# Motor_Surucu_V4.net
KiCad netlist of a schematic drawn in EAGLE
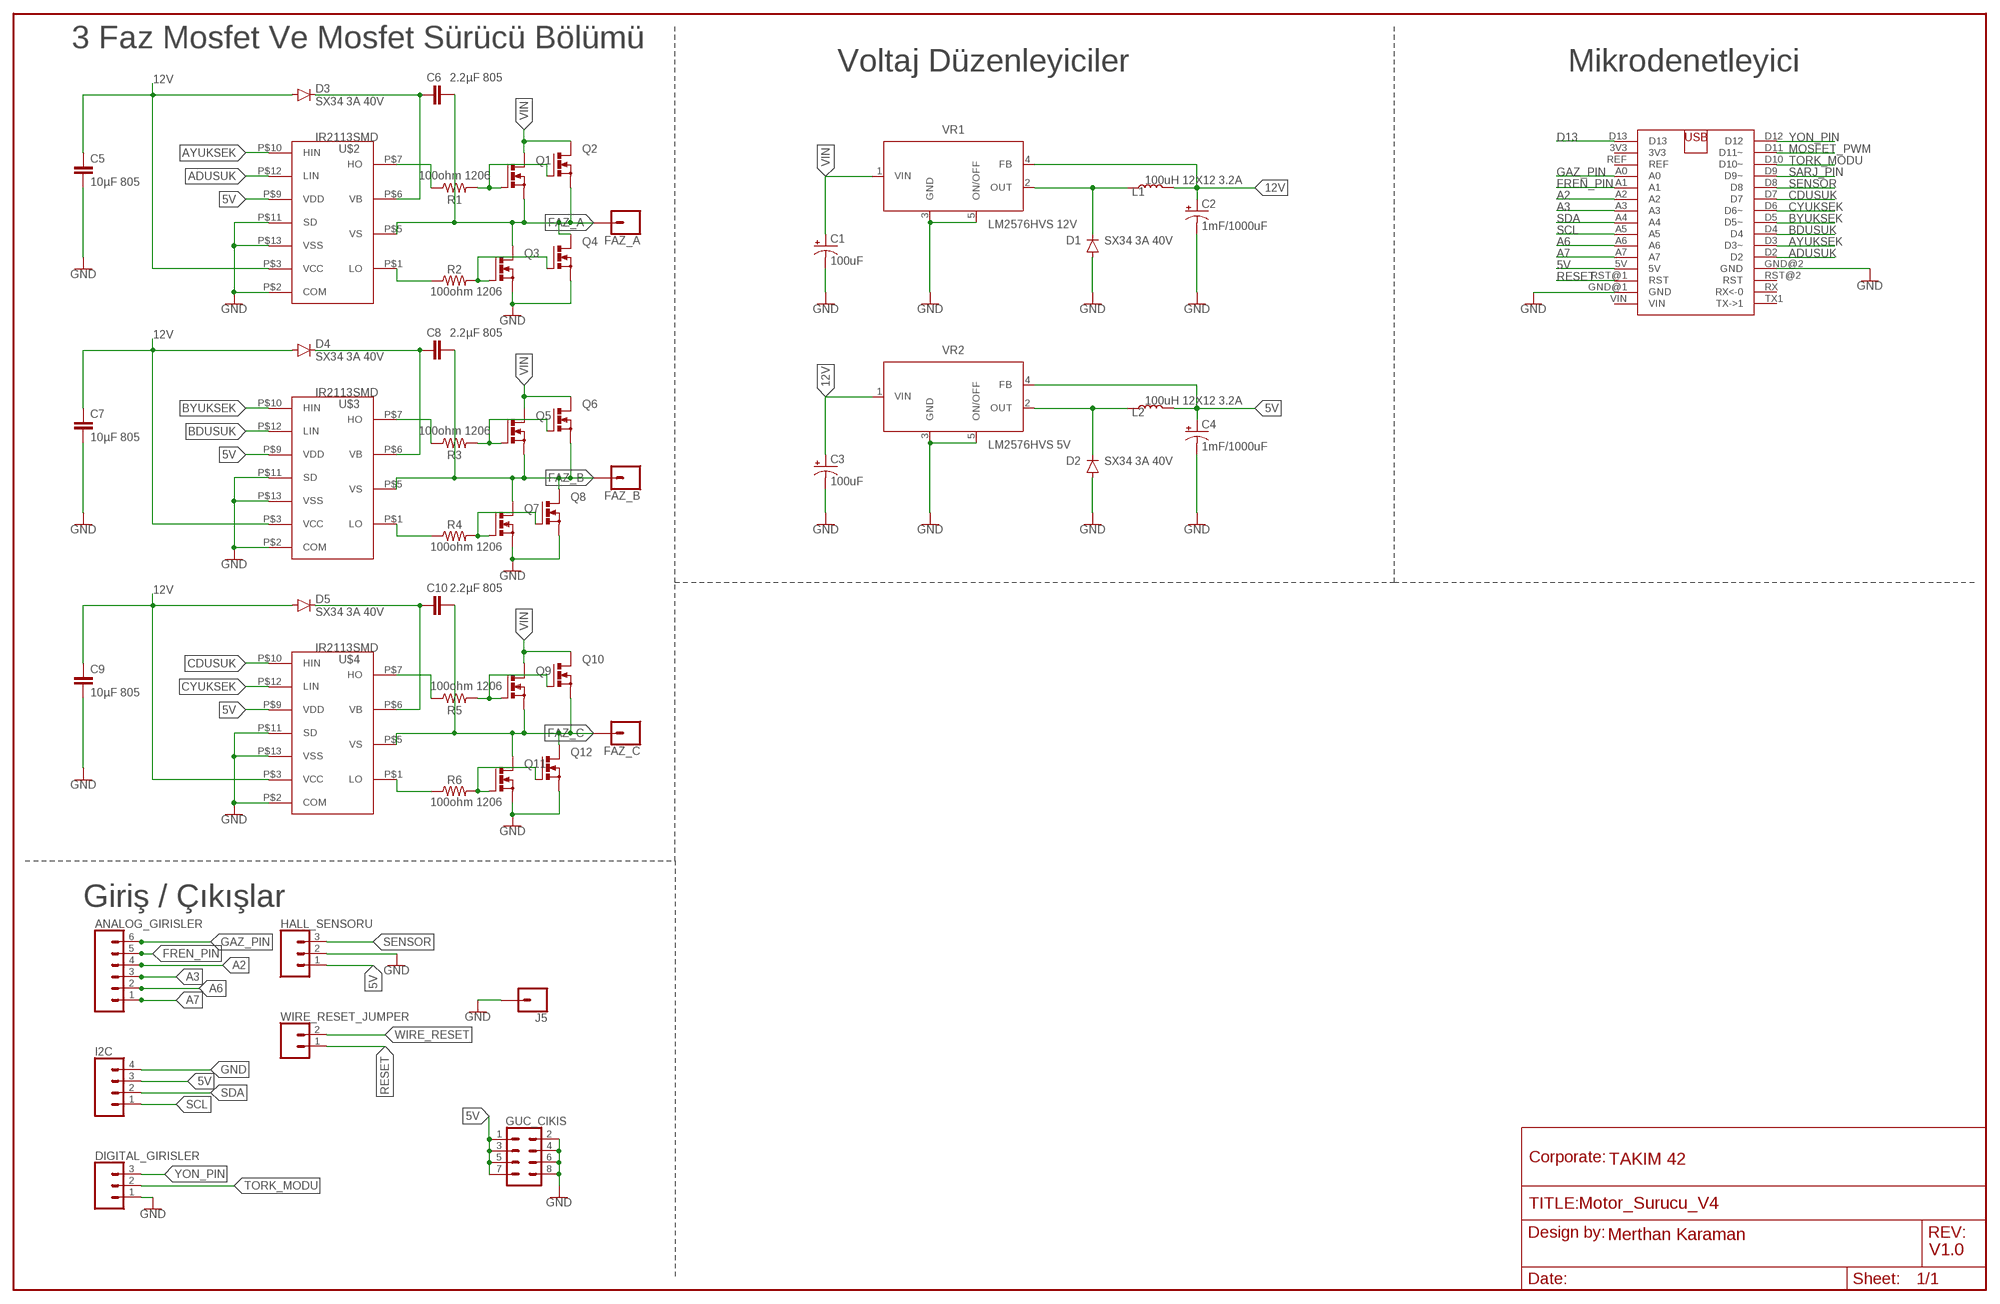
[diagram p0: schematic, sheet 1]

(export (version "E")
  (design (tool "Eeschema 10.0.6"))
  (components
    (comp (ref "ANALOG_GIRISLER")
      (value "CONN_06SILK_FEMALE_PTH")
      (footprint "eagle-import:1X06")
      (libsource (lib "eagle-import") (part "CONN_06SILK_FEMALE_PTH"))
    )
    (comp (ref "C1")
      (value "100uF")
      (footprint "eagle-import:CPOL-RADIAL-2.5MM-6.5MM")
      (libsource (lib "eagle-import") (part "100UF-POLAR-RADIAL-2.5MM-25V-20%"))
    )
    (comp (ref "C2")
      (value "1mF/1000uF")
      (footprint "eagle-import:PANASONIC_G")
      (libsource (lib "eagle-import") (part "560UF-PANASONIC_G-25V-20%"))
    )
    (comp (ref "C3")
      (value "100uF")
      (footprint "eagle-import:CPOL-RADIAL-2.5MM-6.5MM")
      (libsource (lib "eagle-import") (part "100UF-POLAR-RADIAL-2.5MM-25V-20%"))
    )
    (comp (ref "C4")
      (value "1mF/1000uF")
      (footprint "eagle-import:PANASONIC_G")
      (libsource (lib "eagle-import") (part "560UF-PANASONIC_G-25V-20%"))
    )
    (comp (ref "C5")
      (value "10µF 805")
      (footprint "eagle-import:0805")
      (libsource (lib "eagle-import") (part "0.33UF/330NF-0805-50V-10%"))
    )
    (comp (ref "C6")
      (value "2.2µF 805")
      (footprint "eagle-import:0805")
      (libsource (lib "eagle-import") (part "0.33UF/330NF-0805-50V-10%"))
    )
    (comp (ref "C7")
      (value "10µF 805")
      (footprint "eagle-import:0805")
      (libsource (lib "eagle-import") (part "0.33UF/330NF-0805-50V-10%"))
    )
    (comp (ref "C8")
      (value "2.2µF 805")
      (footprint "eagle-import:0805")
      (libsource (lib "eagle-import") (part "0.33UF/330NF-0805-50V-10%"))
    )
    (comp (ref "C9")
      (value "10µF 805")
      (footprint "eagle-import:0805")
      (libsource (lib "eagle-import") (part "0.33UF/330NF-0805-50V-10%"))
    )
    (comp (ref "C10")
      (value "2.2µF 805")
      (footprint "eagle-import:0805")
      (libsource (lib "eagle-import") (part "0.33UF/330NF-0805-50V-10%"))
    )
    (comp (ref "D1")
      (value "SX34 3A 40V")
      (footprint "eagle-import:DO214AC")
      (libsource (lib "eagle-import") (part "DIODE-DO214AC"))
    )
    (comp (ref "D2")
      (value "SX34 3A 40V")
      (footprint "eagle-import:DO214AC")
      (libsource (lib "eagle-import") (part "DIODE-DO214AC"))
    )
    (comp (ref "D3")
      (value "SX34 3A 40V")
      (footprint "eagle-import:DO214AC")
      (libsource (lib "eagle-import") (part "DIODE-DO214AC"))
    )
    (comp (ref "D4")
      (value "SX34 3A 40V")
      (footprint "eagle-import:DO214AC")
      (libsource (lib "eagle-import") (part "DIODE-DO214AC"))
    )
    (comp (ref "D5")
      (value "SX34 3A 40V")
      (footprint "eagle-import:DO214AC")
      (libsource (lib "eagle-import") (part "DIODE-DO214AC"))
    )
    (comp (ref "DIGITAL_GIRISLER")
      (value "CONN_03")
      (footprint "eagle-import:1X03")
      (libsource (lib "eagle-import") (part "CONN_03"))
    )
    (comp (ref "FAZ_A")
      (value "CONN_01SNAP-MALE")
      (footprint "eagle-import:SNAP-MALE")
      (libsource (lib "eagle-import") (part "CONN_01SNAP-MALE"))
    )
    (comp (ref "FAZ_B")
      (value "CONN_01SNAP-MALE")
      (footprint "eagle-import:SNAP-MALE")
      (libsource (lib "eagle-import") (part "CONN_01SNAP-MALE"))
    )
    (comp (ref "FAZ_C")
      (value "CONN_01SNAP-MALE")
      (footprint "eagle-import:SNAP-MALE")
      (libsource (lib "eagle-import") (part "CONN_01SNAP-MALE"))
    )
    (comp (ref "GUC_CIKIS")
      (value "CONN_04X2")
      (footprint "eagle-import:2X4")
      (libsource (lib "eagle-import") (part "CONN_04X2"))
    )
    (comp (ref "HALL_SENSORU")
      (value "CONN_03")
      (footprint "eagle-import:1X03")
      (libsource (lib "eagle-import") (part "CONN_03"))
    )
    (comp (ref "I2C")
      (value "CONN_04")
      (footprint "eagle-import:1X04")
      (libsource (lib "eagle-import") (part "CONN_04"))
    )
    (comp (ref "J5")
      (value "CONN_01SNAP-MALE")
      (footprint "eagle-import:SNAP-MALE")
      (libsource (lib "eagle-import") (part "CONN_01SNAP-MALE"))
    )
    (comp (ref "L1")
      (value "100uH 12X12 3.2A")
      (footprint "eagle-import:INDUCTOR_SDR1307")
      (libsource (lib "eagle-import") (part "INDUCTOR-SDR13-27UH"))
    )
    (comp (ref "L2")
      (value "100uH 12X12 3.2A")
      (footprint "eagle-import:INDUCTOR_SDR1307")
      (libsource (lib "eagle-import") (part "INDUCTOR-SDR13-27UH"))
    )
    (comp (ref "Q1")
      (value "PMOSFET_NTO220BV")
      (footprint "eagle-import:TO220BV")
      (libsource (lib "eagle-import") (part "PMOSFET_NTO220BV"))
    )
    (comp (ref "Q2")
      (value "PMOSFET_NTO220BV")
      (footprint "eagle-import:TO220BV")
      (libsource (lib "eagle-import") (part "PMOSFET_NTO220BV"))
    )
    (comp (ref "Q3")
      (value "PMOSFET_NTO220BV")
      (footprint "eagle-import:TO220BV")
      (libsource (lib "eagle-import") (part "PMOSFET_NTO220BV"))
    )
    (comp (ref "Q4")
      (value "PMOSFET_NTO220BV")
      (footprint "eagle-import:TO220BV")
      (libsource (lib "eagle-import") (part "PMOSFET_NTO220BV"))
    )
    (comp (ref "Q5")
      (value "PMOSFET_NTO220BV")
      (footprint "eagle-import:TO220BV")
      (libsource (lib "eagle-import") (part "PMOSFET_NTO220BV"))
    )
    (comp (ref "Q6")
      (value "PMOSFET_NTO220BV")
      (footprint "eagle-import:TO220BV")
      (libsource (lib "eagle-import") (part "PMOSFET_NTO220BV"))
    )
    (comp (ref "Q7")
      (value "PMOSFET_NTO220BV")
      (footprint "eagle-import:TO220BV")
      (libsource (lib "eagle-import") (part "PMOSFET_NTO220BV"))
    )
    (comp (ref "Q8")
      (value "PMOSFET_NTO220BV")
      (footprint "eagle-import:TO220BV")
      (libsource (lib "eagle-import") (part "PMOSFET_NTO220BV"))
    )
    (comp (ref "Q9")
      (value "PMOSFET_NTO220BV")
      (footprint "eagle-import:TO220BV")
      (libsource (lib "eagle-import") (part "PMOSFET_NTO220BV"))
    )
    (comp (ref "Q10")
      (value "PMOSFET_NTO220BV")
      (footprint "eagle-import:TO220BV")
      (libsource (lib "eagle-import") (part "PMOSFET_NTO220BV"))
    )
    (comp (ref "Q11")
      (value "PMOSFET_NTO220BV")
      (footprint "eagle-import:TO220BV")
      (libsource (lib "eagle-import") (part "PMOSFET_NTO220BV"))
    )
    (comp (ref "Q12")
      (value "PMOSFET_NTO220BV")
      (footprint "eagle-import:TO220BV")
      (libsource (lib "eagle-import") (part "PMOSFET_NTO220BV"))
    )
    (comp (ref "R1")
      (value "100ohm 1206")
      (footprint "eagle-import:1206")
      (libsource (lib "eagle-import") (part "RESISTOR1206"))
    )
    (comp (ref "R2")
      (value "100ohm 1206")
      (footprint "eagle-import:1206")
      (libsource (lib "eagle-import") (part "RESISTOR1206"))
    )
    (comp (ref "R3")
      (value "100ohm 1206")
      (footprint "eagle-import:1206")
      (libsource (lib "eagle-import") (part "RESISTOR1206"))
    )
    (comp (ref "R4")
      (value "100ohm 1206")
      (footprint "eagle-import:1206")
      (libsource (lib "eagle-import") (part "RESISTOR1206"))
    )
    (comp (ref "R5")
      (value "100ohm 1206")
      (footprint "eagle-import:1206")
      (libsource (lib "eagle-import") (part "RESISTOR1206"))
    )
    (comp (ref "R6")
      (value "100ohm 1206")
      (footprint "eagle-import:1206")
      (libsource (lib "eagle-import") (part "RESISTOR1206"))
    )
    (comp (ref "U$1")
      (value "ARDUINO_NANO")
      (footprint "eagle-import:ARDUINO_NANO")
      (libsource (lib "eagle-import") (part "ARDUINO_NANO"))
    )
    (comp (ref "U$2")
      (value "IR2113SMD")
      (footprint "eagle-import:SOIC-14")
      (libsource (lib "eagle-import") (part "IR2113SMD"))
    )
    (comp (ref "U$3")
      (value "IR2113SMD")
      (footprint "eagle-import:SOIC-14")
      (libsource (lib "eagle-import") (part "IR2113SMD"))
    )
    (comp (ref "U$4")
      (value "IR2113SMD")
      (footprint "eagle-import:SOIC-14")
      (libsource (lib "eagle-import") (part "IR2113SMD"))
    )
    (comp (ref "VR1")
      (value "LM2576HVS 12V")
      (footprint "eagle-import:TO170P1435X465-6N")
      (fields (field (name "MANUFACTURER") "TI") (field (name "MPN") "LM2576HVS-5.0/NOPB"))
      (libsource (lib "eagle-import") (part "LM2576HVS-5.0/NOPBTO-263"))
    )
    (comp (ref "VR2")
      (value "LM2576HVS 5V")
      (footprint "eagle-import:TO170P1435X465-6N")
      (fields (field (name "MANUFACTURER") "TI") (field (name "MPN") "LM2576HVS-5.0/NOPB"))
      (libsource (lib "eagle-import") (part "LM2576HVS-5.0/NOPBTO-263"))
    )
    (comp (ref "WIRE_RESET_JUMPER")
      (value "CONN_02")
      (footprint "eagle-import:1X02")
      (libsource (lib "eagle-import") (part "CONN_02"))
    )
  )
  (nets
    (net (code "1") (name "/D13") (class "Default")
      (node (ref "U$1") (pin "D13") (pinfunction "D13_D13") (pintype "bidirectional"))
    )
    (net (code "2") (name "/MOSFET_PWM") (class "Default")
      (node (ref "U$1") (pin "D11") (pinfunction "D11~{}_D11") (pintype "bidirectional"))
    )
    (net (code "3") (name "/SARJ_PIN") (class "Default")
      (node (ref "U$1") (pin "D9") (pinfunction "D9~{}_D9") (pintype "bidirectional"))
    )
    (net (code "4") (name "5V") (class "Default")
      (node (ref "C4") (pin "+") (pinfunction "+_+") (pintype "passive"))
      (node (ref "GUC_CIKIS") (pin "1") (pinfunction "1_1") (pintype "passive"))
      (node (ref "GUC_CIKIS") (pin "3") (pinfunction "3_3") (pintype "passive"))
      (node (ref "GUC_CIKIS") (pin "5") (pinfunction "5_5") (pintype "passive"))
      (node (ref "GUC_CIKIS") (pin "7") (pinfunction "7_7") (pintype "passive"))
      (node (ref "HALL_SENSORU") (pin "1") (pinfunction "1_1") (pintype "passive"))
      (node (ref "I2C") (pin "3") (pinfunction "3_3") (pintype "passive"))
      (node (ref "L2") (pin "P$2") (pinfunction "2_P$2") (pintype "passive"))
      (node (ref "U$1") (pin "5V") (pinfunction "5V_5V") (pintype "bidirectional"))
      (node (ref "U$2") (pin "P$9") (pinfunction "VDD_P$9") (pintype "bidirectional"))
      (node (ref "U$3") (pin "P$9") (pinfunction "VDD_P$9") (pintype "bidirectional"))
      (node (ref "U$4") (pin "P$9") (pinfunction "VDD_P$9") (pintype "bidirectional"))
      (node (ref "VR2") (pin "4") (pinfunction "FB_4") (pintype "output"))
    )
    (net (code "5") (name "12V") (class "Default")
      (node (ref "C2") (pin "+") (pinfunction "+_+") (pintype "passive"))
      (node (ref "C3") (pin "1") (pinfunction "+_1") (pintype "passive"))
      (node (ref "C5") (pin "1") (pinfunction "1_1") (pintype "passive"))
      (node (ref "C7") (pin "1") (pinfunction "1_1") (pintype "passive"))
      (node (ref "C9") (pin "1") (pinfunction "1_1") (pintype "passive"))
      (node (ref "D3") (pin "A") (pinfunction "A_A") (pintype "passive"))
      (node (ref "D4") (pin "A") (pinfunction "A_A") (pintype "passive"))
      (node (ref "D5") (pin "A") (pinfunction "A_A") (pintype "passive"))
      (node (ref "L1") (pin "P$2") (pinfunction "2_P$2") (pintype "passive"))
      (node (ref "U$2") (pin "P$3") (pinfunction "VCC_P$3") (pintype "bidirectional"))
      (node (ref "U$3") (pin "P$3") (pinfunction "VCC_P$3") (pintype "bidirectional"))
      (node (ref "U$4") (pin "P$3") (pinfunction "VCC_P$3") (pintype "bidirectional"))
      (node (ref "VR1") (pin "4") (pinfunction "FB_4") (pintype "output"))
      (node (ref "VR2") (pin "1") (pinfunction "VIN_1") (pintype "input"))
    )
    (net (code "6") (name "A2") (class "Default")
      (node (ref "ANALOG_GIRISLER") (pin "4") (pinfunction "4_4") (pintype "passive"))
      (node (ref "U$1") (pin "A2") (pinfunction "A2_A2") (pintype "bidirectional"))
    )
    (net (code "7") (name "A3") (class "Default")
      (node (ref "ANALOG_GIRISLER") (pin "3") (pinfunction "3_3") (pintype "passive"))
      (node (ref "U$1") (pin "A3") (pinfunction "A3_A3") (pintype "bidirectional"))
    )
    (net (code "8") (name "A6") (class "Default")
      (node (ref "ANALOG_GIRISLER") (pin "2") (pinfunction "2_2") (pintype "passive"))
      (node (ref "U$1") (pin "A6") (pinfunction "A6_A6") (pintype "bidirectional"))
    )
    (net (code "9") (name "A7") (class "Default")
      (node (ref "ANALOG_GIRISLER") (pin "1") (pinfunction "1_1") (pintype "passive"))
      (node (ref "U$1") (pin "A7") (pinfunction "A7_A7") (pintype "bidirectional"))
    )
    (net (code "10") (name "ADUSUK") (class "Default")
      (node (ref "U$1") (pin "D2") (pinfunction "D2_D2") (pintype "bidirectional"))
      (node (ref "U$2") (pin "P$12") (pinfunction "LIN_P$12") (pintype "bidirectional"))
    )
    (net (code "11") (name "AYUKSEK") (class "Default")
      (node (ref "U$1") (pin "D3") (pinfunction "D3~{}_D3") (pintype "bidirectional"))
      (node (ref "U$2") (pin "P$10") (pinfunction "HIN_P$10") (pintype "bidirectional"))
    )
    (net (code "12") (name "BDUSUK") (class "Default")
      (node (ref "U$1") (pin "D4") (pinfunction "D4_D4") (pintype "bidirectional"))
      (node (ref "U$3") (pin "P$12") (pinfunction "LIN_P$12") (pintype "bidirectional"))
    )
    (net (code "13") (name "BYUKSEK") (class "Default")
      (node (ref "U$1") (pin "D5") (pinfunction "D5~{}_D5") (pintype "bidirectional"))
      (node (ref "U$3") (pin "P$10") (pinfunction "HIN_P$10") (pintype "bidirectional"))
    )
    (net (code "14") (name "CDUSUK") (class "Default")
      (node (ref "U$1") (pin "D7") (pinfunction "D7_D7") (pintype "bidirectional"))
      (node (ref "U$4") (pin "P$10") (pinfunction "HIN_P$10") (pintype "bidirectional"))
    )
    (net (code "15") (name "CYUKSEK") (class "Default")
      (node (ref "U$1") (pin "D6") (pinfunction "D6~{}_D6") (pintype "bidirectional"))
      (node (ref "U$4") (pin "P$12") (pinfunction "LIN_P$12") (pintype "bidirectional"))
    )
    (net (code "16") (name "FAZ_A") (class "Default")
      (node (ref "C6") (pin "2") (pinfunction "2_2") (pintype "passive"))
      (node (ref "FAZ_A") (pin "2") (pinfunction "1_2") (pintype "passive"))
      (node (ref "Q1") (pin "S") (pinfunction "S_S") (pintype "passive"))
      (node (ref "Q2") (pin "S") (pinfunction "S_S") (pintype "passive"))
      (node (ref "Q3") (pin "D") (pinfunction "D_D") (pintype "passive"))
      (node (ref "Q4") (pin "D") (pinfunction "D_D") (pintype "passive"))
      (node (ref "U$2") (pin "P$5") (pinfunction "VS_P$5") (pintype "bidirectional"))
    )
    (net (code "17") (name "FAZ_B") (class "Default")
      (node (ref "C8") (pin "2") (pinfunction "2_2") (pintype "passive"))
      (node (ref "FAZ_B") (pin "2") (pinfunction "1_2") (pintype "passive"))
      (node (ref "Q5") (pin "S") (pinfunction "S_S") (pintype "passive"))
      (node (ref "Q6") (pin "S") (pinfunction "S_S") (pintype "passive"))
      (node (ref "Q7") (pin "D") (pinfunction "D_D") (pintype "passive"))
      (node (ref "Q8") (pin "D") (pinfunction "D_D") (pintype "passive"))
      (node (ref "U$3") (pin "P$5") (pinfunction "VS_P$5") (pintype "bidirectional"))
    )
    (net (code "18") (name "FAZ_C") (class "Default")
      (node (ref "C10") (pin "2") (pinfunction "2_2") (pintype "passive"))
      (node (ref "FAZ_C") (pin "2") (pinfunction "1_2") (pintype "passive"))
      (node (ref "Q10") (pin "S") (pinfunction "S_S") (pintype "passive"))
      (node (ref "Q11") (pin "D") (pinfunction "D_D") (pintype "passive"))
      (node (ref "Q12") (pin "D") (pinfunction "D_D") (pintype "passive"))
      (node (ref "Q9") (pin "S") (pinfunction "S_S") (pintype "passive"))
      (node (ref "U$4") (pin "P$5") (pinfunction "VS_P$5") (pintype "bidirectional"))
    )
    (net (code "19") (name "FREN_PIN") (class "Default")
      (node (ref "ANALOG_GIRISLER") (pin "5") (pinfunction "5_5") (pintype "passive"))
      (node (ref "U$1") (pin "A1") (pinfunction "A1_A1") (pintype "bidirectional"))
    )
    (net (code "20") (name "GAZ_PIN") (class "Default")
      (node (ref "ANALOG_GIRISLER") (pin "6") (pinfunction "6_6") (pintype "passive"))
      (node (ref "U$1") (pin "A0") (pinfunction "A0_A0") (pintype "bidirectional"))
    )
    (net (code "21") (name "GND") (class "Default")
      (node (ref "C1") (pin "2") (pinfunction "-_2") (pintype "passive"))
      (node (ref "C2") (pin "-") (pinfunction "-_-") (pintype "passive"))
      (node (ref "C3") (pin "2") (pinfunction "-_2") (pintype "passive"))
      (node (ref "C4") (pin "-") (pinfunction "-_-") (pintype "passive"))
      (node (ref "C5") (pin "2") (pinfunction "2_2") (pintype "passive"))
      (node (ref "C7") (pin "2") (pinfunction "2_2") (pintype "passive"))
      (node (ref "C9") (pin "2") (pinfunction "2_2") (pintype "passive"))
      (node (ref "D1") (pin "A") (pinfunction "A_A") (pintype "passive"))
      (node (ref "D2") (pin "A") (pinfunction "A_A") (pintype "passive"))
      (node (ref "DIGITAL_GIRISLER") (pin "1") (pinfunction "1_1") (pintype "passive"))
      (node (ref "GUC_CIKIS") (pin "2") (pinfunction "2_2") (pintype "passive"))
      (node (ref "GUC_CIKIS") (pin "4") (pinfunction "4_4") (pintype "passive"))
      (node (ref "GUC_CIKIS") (pin "6") (pinfunction "6_6") (pintype "passive"))
      (node (ref "GUC_CIKIS") (pin "8") (pinfunction "8_8") (pintype "passive"))
      (node (ref "HALL_SENSORU") (pin "2") (pinfunction "2_2") (pintype "passive"))
      (node (ref "I2C") (pin "4") (pinfunction "4_4") (pintype "passive"))
      (node (ref "J5") (pin "2") (pinfunction "1_2") (pintype "passive"))
      (node (ref "Q11") (pin "S") (pinfunction "S_S") (pintype "passive"))
      (node (ref "Q12") (pin "S") (pinfunction "S_S") (pintype "passive"))
      (node (ref "Q3") (pin "S") (pinfunction "S_S") (pintype "passive"))
      (node (ref "Q4") (pin "S") (pinfunction "S_S") (pintype "passive"))
      (node (ref "Q7") (pin "S") (pinfunction "S_S") (pintype "passive"))
      (node (ref "Q8") (pin "S") (pinfunction "S_S") (pintype "passive"))
      (node (ref "U$1") (pin "GND@1") (pinfunction "GND_GND@1") (pintype "bidirectional"))
      (node (ref "U$1") (pin "GND@2") (pinfunction "GND_GND@2") (pintype "bidirectional"))
      (node (ref "U$2") (pin "P$11") (pinfunction "SD_P$11") (pintype "bidirectional"))
      (node (ref "U$2") (pin "P$13") (pinfunction "VSS_P$13") (pintype "bidirectional"))
      (node (ref "U$2") (pin "P$2") (pinfunction "COM_P$2") (pintype "bidirectional"))
      (node (ref "U$3") (pin "P$11") (pinfunction "SD_P$11") (pintype "bidirectional"))
      (node (ref "U$3") (pin "P$13") (pinfunction "VSS_P$13") (pintype "bidirectional"))
      (node (ref "U$3") (pin "P$2") (pinfunction "COM_P$2") (pintype "bidirectional"))
      (node (ref "U$4") (pin "P$11") (pinfunction "SD_P$11") (pintype "bidirectional"))
      (node (ref "U$4") (pin "P$13") (pinfunction "VSS_P$13") (pintype "bidirectional"))
      (node (ref "U$4") (pin "P$2") (pinfunction "COM_P$2") (pintype "bidirectional"))
      (node (ref "VR1") (pin "3") (pinfunction "GND_3") (pintype "passive"))
      (node (ref "VR1") (pin "5") (pinfunction "ON/OFF_5") (pintype "input"))
      (node (ref "VR2") (pin "3") (pinfunction "GND_3") (pintype "passive"))
      (node (ref "VR2") (pin "5") (pinfunction "ON/OFF_5") (pintype "input"))
    )
    (net (code "22") (name "Net-(L1-1)") (class "Default")
      (node (ref "D1") (pin "C") (pinfunction "C_C") (pintype "passive"))
      (node (ref "L1") (pin "P$1") (pinfunction "1_P$1") (pintype "passive"))
      (node (ref "VR1") (pin "2") (pinfunction "OUT_2") (pintype "output"))
    )
    (net (code "23") (name "Net-(L2-1)") (class "Default")
      (node (ref "D2") (pin "C") (pinfunction "C_C") (pintype "passive"))
      (node (ref "L2") (pin "P$1") (pinfunction "1_P$1") (pintype "passive"))
      (node (ref "VR2") (pin "2") (pinfunction "OUT_2") (pintype "output"))
    )
    (net (code "24") (name "Net-(Q1-PadG)") (class "Default")
      (node (ref "Q1") (pin "G") (pinfunction "G_G") (pintype "passive"))
      (node (ref "Q2") (pin "G") (pinfunction "G_G") (pintype "passive"))
      (node (ref "R1") (pin "2") (pinfunction "2_2") (pintype "passive"))
    )
    (net (code "25") (name "Net-(Q3-PadG)") (class "Default")
      (node (ref "Q3") (pin "G") (pinfunction "G_G") (pintype "passive"))
      (node (ref "Q4") (pin "G") (pinfunction "G_G") (pintype "passive"))
      (node (ref "R2") (pin "2") (pinfunction "2_2") (pintype "passive"))
    )
    (net (code "26") (name "Net-(Q5-PadG)") (class "Default")
      (node (ref "Q5") (pin "G") (pinfunction "G_G") (pintype "passive"))
      (node (ref "Q6") (pin "G") (pinfunction "G_G") (pintype "passive"))
      (node (ref "R3") (pin "2") (pinfunction "2_2") (pintype "passive"))
    )
    (net (code "27") (name "Net-(Q7-PadG)") (class "Default")
      (node (ref "Q7") (pin "G") (pinfunction "G_G") (pintype "passive"))
      (node (ref "Q8") (pin "G") (pinfunction "G_G") (pintype "passive"))
      (node (ref "R4") (pin "2") (pinfunction "2_2") (pintype "passive"))
    )
    (net (code "28") (name "Net-(Q10-PadG)") (class "Default")
      (node (ref "Q10") (pin "G") (pinfunction "G_G") (pintype "passive"))
      (node (ref "Q9") (pin "G") (pinfunction "G_G") (pintype "passive"))
      (node (ref "R5") (pin "2") (pinfunction "2_2") (pintype "passive"))
    )
    (net (code "29") (name "Net-(Q11-PadG)") (class "Default")
      (node (ref "Q11") (pin "G") (pinfunction "G_G") (pintype "passive"))
      (node (ref "Q12") (pin "G") (pinfunction "G_G") (pintype "passive"))
      (node (ref "R6") (pin "2") (pinfunction "2_2") (pintype "passive"))
    )
    (net (code "30") (name "Net-(U$2-HO)") (class "Default")
      (node (ref "R1") (pin "1") (pinfunction "1_1") (pintype "passive"))
      (node (ref "U$2") (pin "P$7") (pinfunction "HO_P$7") (pintype "bidirectional"))
    )
    (net (code "31") (name "Net-(U$2-LO)") (class "Default")
      (node (ref "R2") (pin "1") (pinfunction "1_1") (pintype "passive"))
      (node (ref "U$2") (pin "P$1") (pinfunction "LO_P$1") (pintype "bidirectional"))
    )
    (net (code "32") (name "Net-(U$2-VB)") (class "Default")
      (node (ref "C6") (pin "1") (pinfunction "1_1") (pintype "passive"))
      (node (ref "D3") (pin "C") (pinfunction "C_C") (pintype "passive"))
      (node (ref "U$2") (pin "P$6") (pinfunction "VB_P$6") (pintype "bidirectional"))
    )
    (net (code "33") (name "Net-(U$3-HO)") (class "Default")
      (node (ref "R3") (pin "1") (pinfunction "1_1") (pintype "passive"))
      (node (ref "U$3") (pin "P$7") (pinfunction "HO_P$7") (pintype "bidirectional"))
    )
    (net (code "34") (name "Net-(U$3-LO)") (class "Default")
      (node (ref "R4") (pin "1") (pinfunction "1_1") (pintype "passive"))
      (node (ref "U$3") (pin "P$1") (pinfunction "LO_P$1") (pintype "bidirectional"))
    )
    (net (code "35") (name "Net-(U$3-VB)") (class "Default")
      (node (ref "C8") (pin "1") (pinfunction "1_1") (pintype "passive"))
      (node (ref "D4") (pin "C") (pinfunction "C_C") (pintype "passive"))
      (node (ref "U$3") (pin "P$6") (pinfunction "VB_P$6") (pintype "bidirectional"))
    )
    (net (code "36") (name "Net-(U$4-HO)") (class "Default")
      (node (ref "R5") (pin "1") (pinfunction "1_1") (pintype "passive"))
      (node (ref "U$4") (pin "P$7") (pinfunction "HO_P$7") (pintype "bidirectional"))
    )
    (net (code "37") (name "Net-(U$4-LO)") (class "Default")
      (node (ref "R6") (pin "1") (pinfunction "1_1") (pintype "passive"))
      (node (ref "U$4") (pin "P$1") (pinfunction "LO_P$1") (pintype "bidirectional"))
    )
    (net (code "38") (name "Net-(U$4-VB)") (class "Default")
      (node (ref "C10") (pin "1") (pinfunction "1_1") (pintype "passive"))
      (node (ref "D5") (pin "C") (pinfunction "C_C") (pintype "passive"))
      (node (ref "U$4") (pin "P$6") (pinfunction "VB_P$6") (pintype "bidirectional"))
    )
    (net (code "39") (name "RESET") (class "Default")
      (node (ref "U$1") (pin "RST@1") (pinfunction "RST_RST@1") (pintype "bidirectional"))
      (node (ref "WIRE_RESET_JUMPER") (pin "1") (pinfunction "1_1") (pintype "passive"))
    )
    (net (code "40") (name "SCL") (class "Default")
      (node (ref "I2C") (pin "1") (pinfunction "1_1") (pintype "passive"))
      (node (ref "U$1") (pin "A5") (pinfunction "A5_A5") (pintype "bidirectional"))
    )
    (net (code "41") (name "SDA") (class "Default")
      (node (ref "I2C") (pin "2") (pinfunction "2_2") (pintype "passive"))
      (node (ref "U$1") (pin "A4") (pinfunction "A4_A4") (pintype "bidirectional"))
    )
    (net (code "42") (name "SENSOR") (class "Default")
      (node (ref "HALL_SENSORU") (pin "3") (pinfunction "3_3") (pintype "passive"))
      (node (ref "U$1") (pin "D8") (pinfunction "D8_D8") (pintype "bidirectional"))
    )
    (net (code "43") (name "TORK_MODU") (class "Default")
      (node (ref "DIGITAL_GIRISLER") (pin "2") (pinfunction "2_2") (pintype "passive"))
      (node (ref "U$1") (pin "D10") (pinfunction "D10~{}_D10") (pintype "bidirectional"))
    )
    (net (code "44") (name "VIN") (class "Default")
      (node (ref "C1") (pin "1") (pinfunction "+_1") (pintype "passive"))
      (node (ref "Q1") (pin "D") (pinfunction "D_D") (pintype "passive"))
      (node (ref "Q10") (pin "D") (pinfunction "D_D") (pintype "passive"))
      (node (ref "Q2") (pin "D") (pinfunction "D_D") (pintype "passive"))
      (node (ref "Q5") (pin "D") (pinfunction "D_D") (pintype "passive"))
      (node (ref "Q6") (pin "D") (pinfunction "D_D") (pintype "passive"))
      (node (ref "Q9") (pin "D") (pinfunction "D_D") (pintype "passive"))
      (node (ref "VR1") (pin "1") (pinfunction "VIN_1") (pintype "input"))
    )
    (net (code "45") (name "WIRE_RESET") (class "Default")
      (node (ref "WIRE_RESET_JUMPER") (pin "2") (pinfunction "2_2") (pintype "passive"))
    )
    (net (code "46") (name "YON_PIN") (class "Default")
      (node (ref "DIGITAL_GIRISLER") (pin "3") (pinfunction "3_3") (pintype "passive"))
      (node (ref "U$1") (pin "D12") (pinfunction "D12_D12") (pintype "bidirectional"))
    )
    (net (code "47") (name "unconnected-(U$1-Pad3V3)") (class "Default")
      (node (ref "U$1") (pin "3V3") (pinfunction "3V3_3V3") (pintype "bidirectional"))
    )
    (net (code "48") (name "unconnected-(U$1-PadREF)") (class "Default")
      (node (ref "U$1") (pin "REF") (pinfunction "REF_REF") (pintype "bidirectional"))
    )
    (net (code "49") (name "unconnected-(U$1-PadVIN)") (class "Default")
      (node (ref "U$1") (pin "VIN") (pinfunction "VIN_VIN") (pintype "bidirectional"))
    )
    (net (code "50") (name "unconnected-(U$1-RST-PadRST@2)") (class "Default")
      (node (ref "U$1") (pin "RST@2") (pinfunction "RST_RST@2") (pintype "bidirectional"))
    )
    (net (code "51") (name "unconnected-(U$1-RX<-0-PadRX)") (class "Default")
      (node (ref "U$1") (pin "RX") (pinfunction "RX<-0_RX") (pintype "bidirectional"))
    )
    (net (code "52") (name "unconnected-(U$1-TX->1-PadTX1)") (class "Default")
      (node (ref "U$1") (pin "TX1") (pinfunction "TX->1_TX1") (pintype "bidirectional"))
    )
  )
)
